# LORA-MODULE.net
KiCad netlist of a schematic drawn in Altium Designer
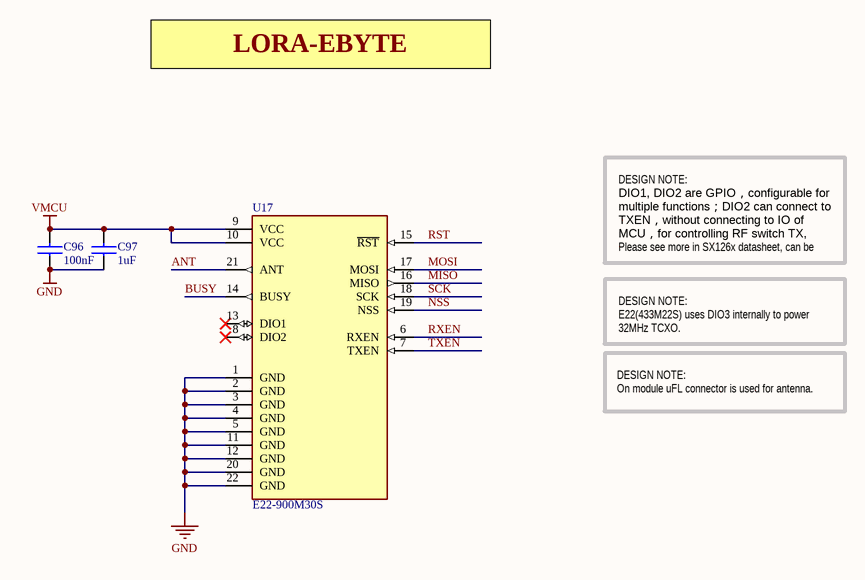
[diagram p0: LORA-MODULE.SchDoc]

(export (version "E")
  (design (tool "Eeschema 10.0.6"))
  (components
    (comp (ref "C96")
      (value "100nF")
      (footprint "CAP0603")
      (description "MURATA - GRM188R71C104KA01J - CAP, MLCC, X7R, 0.1UF, 16V, 0603")
      (fields
        (field (name "MANUFACTURER") "MURATA")
        (field (name "MANUFACTURER PART NUMBER") "GRM188R71C104KA01J")
      )
      (libsource (lib "Passive") (part "C - 100nF"))
    )
    (comp (ref "C97")
      (value "1uF")
      (footprint "CAP0603")
      (description "MURATA - GRM188R61H105KAALD - CAP, MLCC, X5R, 1UF, 50V, 0603")
      (fields
        (field (name "MANUFACTURER") "MURATA")
        (field (name "MANUFACTURER PART NUMBER") "GRM188R61H105KAALD")
      )
      (libsource (lib "Passive") (part "C - 1uF"))
    )
    (comp (ref "U17")
      (value "E22-900M30S")
      (footprint "E22-900M30S")
      (description "SX1262 868/915 MHz 1w SPI LoRa Module")
      (fields (field (name "MF") "EBYTE"))
      (libsource (lib "lib-hiony") (part "E22-900M30S"))
    )
  )
  (nets
    (net (code "1") (name "/ANT") (class "Default")
      (node (ref "U17") (pin "21") (pinfunction "ANT_21") (pintype "output"))
    )
    (net (code "2") (name "/BUSY") (class "Default")
      (node (ref "U17") (pin "14") (pinfunction "BUSY_14") (pintype "output"))
    )
    (net (code "3") (name "/MISO") (class "Default")
      (node (ref "U17") (pin "16") (pinfunction "MISO_16") (pintype "output"))
    )
    (net (code "4") (name "/MOSI") (class "Default")
      (node (ref "U17") (pin "17") (pinfunction "MOSI_17") (pintype "input"))
    )
    (net (code "5") (name "/NSS") (class "Default")
      (node (ref "U17") (pin "19") (pinfunction "NSS_19") (pintype "input"))
    )
    (net (code "6") (name "/RST") (class "Default")
      (node (ref "U17") (pin "15") (pinfunction "~{RST}_15") (pintype "input"))
    )
    (net (code "7") (name "/RXEN") (class "Default")
      (node (ref "U17") (pin "6") (pinfunction "RXEN_6") (pintype "input"))
    )
    (net (code "8") (name "/SCK") (class "Default")
      (node (ref "U17") (pin "18") (pinfunction "SCK_18") (pintype "input"))
    )
    (net (code "9") (name "/TXEN") (class "Default")
      (node (ref "U17") (pin "7") (pinfunction "TXEN_7") (pintype "input"))
    )
    (net (code "10") (name "GND") (class "Default")
      (node (ref "C96") (pin "1") (pinfunction "1_1") (pintype "passive"))
      (node (ref "C97") (pin "1") (pinfunction "1_1") (pintype "passive"))
      (node (ref "U17") (pin "1") (pinfunction "GND_1") (pintype "power_in"))
      (node (ref "U17") (pin "11") (pinfunction "GND_11") (pintype "power_in"))
      (node (ref "U17") (pin "12") (pinfunction "GND_12") (pintype "power_in"))
      (node (ref "U17") (pin "2") (pinfunction "GND_2") (pintype "power_in"))
      (node (ref "U17") (pin "20") (pinfunction "GND_20") (pintype "power_in"))
      (node (ref "U17") (pin "22") (pinfunction "GND_22") (pintype "power_in"))
      (node (ref "U17") (pin "3") (pinfunction "GND_3") (pintype "power_in"))
      (node (ref "U17") (pin "4") (pinfunction "GND_4") (pintype "power_in"))
      (node (ref "U17") (pin "5") (pinfunction "GND_5") (pintype "power_in"))
    )
    (net (code "11") (name "VMCU") (class "Default")
      (node (ref "C96") (pin "2") (pinfunction "2_2") (pintype "passive"))
      (node (ref "C97") (pin "2") (pinfunction "2_2") (pintype "passive"))
      (node (ref "U17") (pin "10") (pinfunction "VCC_10") (pintype "power_in"))
      (node (ref "U17") (pin "9") (pinfunction "VCC_9") (pintype "power_in"))
    )
    (net (code "12") (name "unconnected-(U17-DIO1-Pad13)") (class "Default")
      (node (ref "U17") (pin "13") (pinfunction "DIO1_13") (pintype "bidirectional+no_connect"))
    )
    (net (code "13") (name "unconnected-(U17-DIO2-Pad8)") (class "Default")
      (node (ref "U17") (pin "8") (pinfunction "DIO2_8") (pintype "bidirectional+no_connect"))
    )
  )
)
